# auxboxshield1_7test.net
KiCad netlist of a schematic drawn in EAGLE
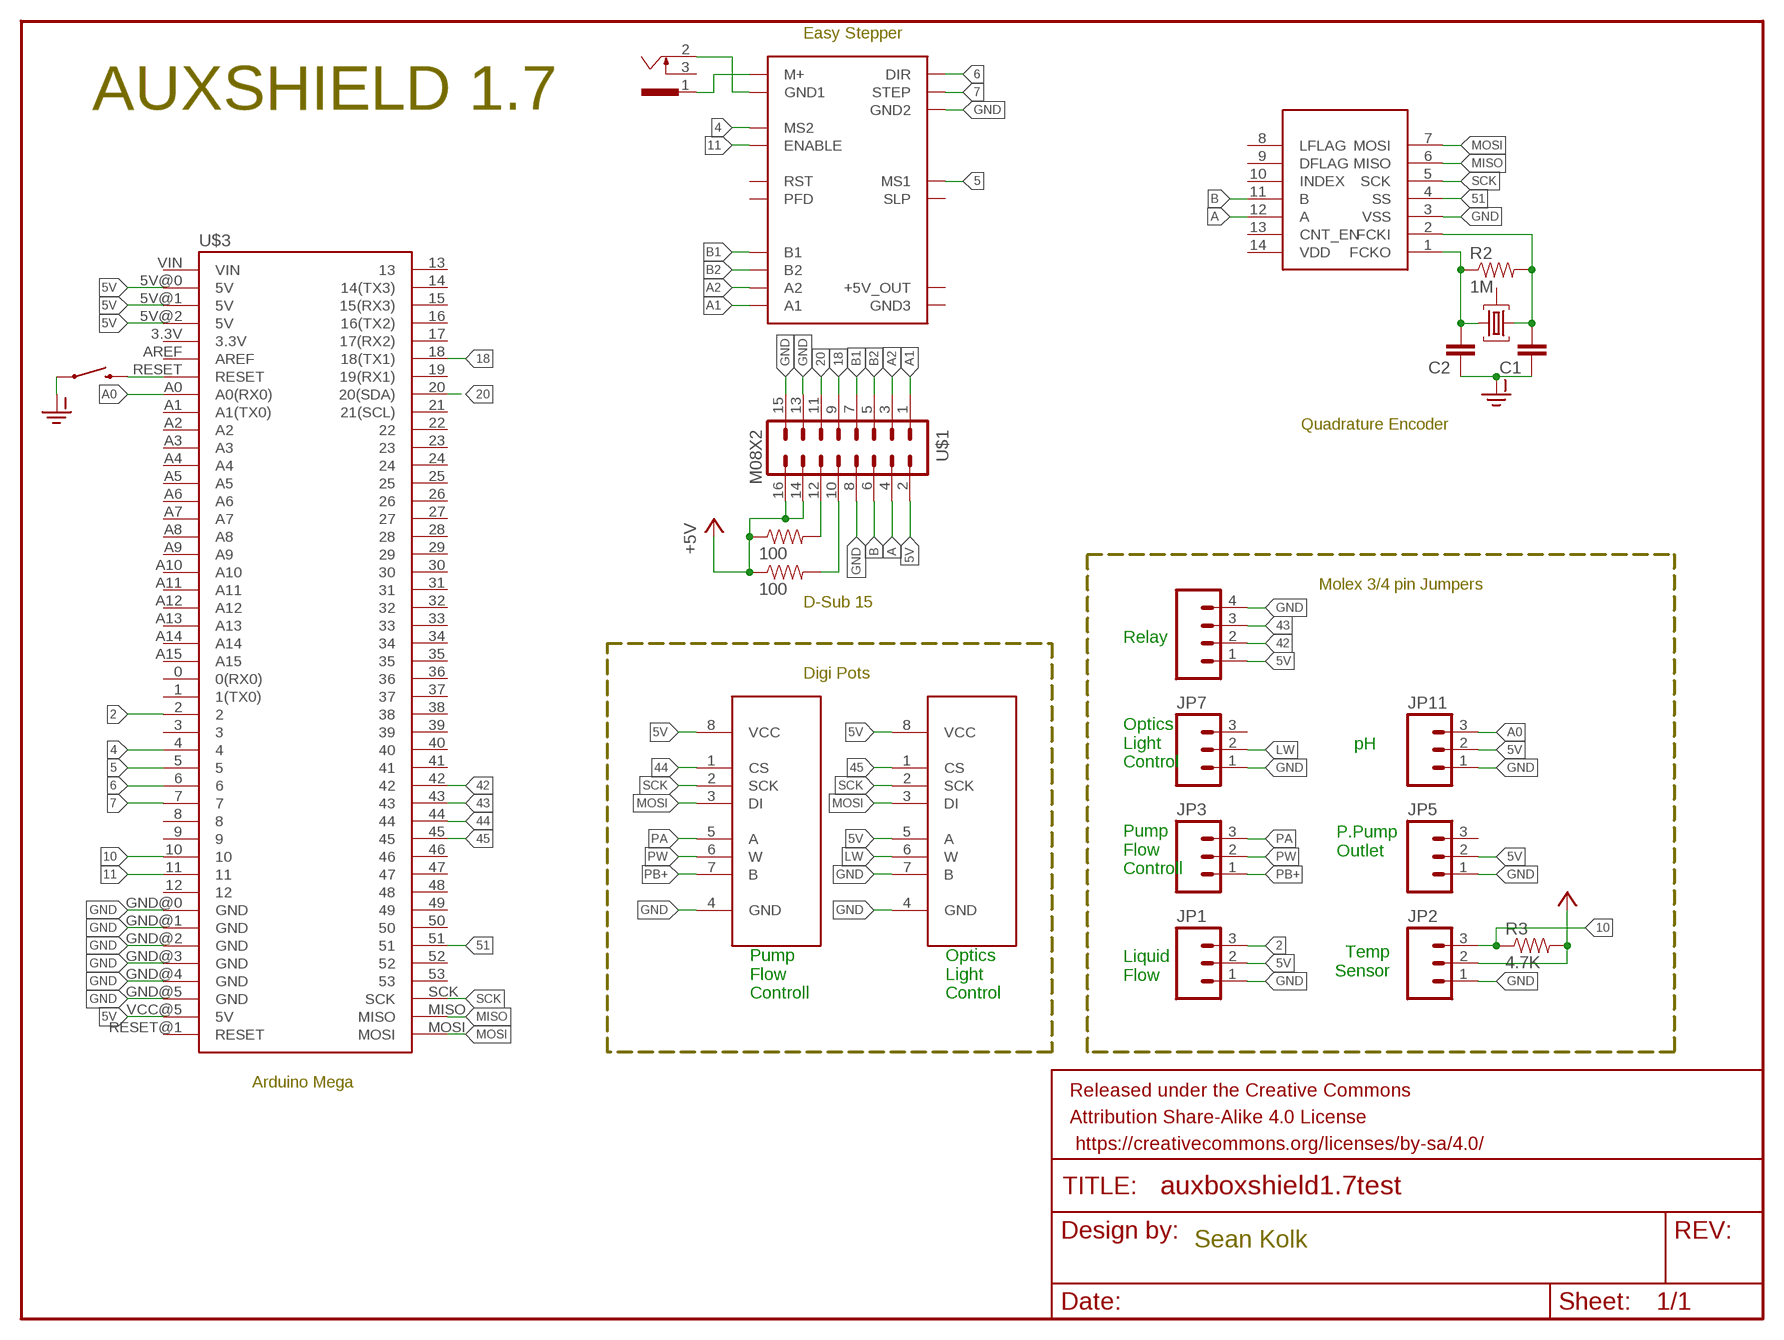
[diagram p0: schematic, sheet 1]

(export (version "E")
  (design (tool "Eeschema 10.0.6"))
  (components
    (comp (ref "C1")
      (value "0.1UF-50V-20%(PTH)KIT-EZ")
      (footprint "eagle-import:CAP-PTH-SMALL-KIT")
      (libsource (lib "eagle-import") (part "0.1UF-50V-20%(PTH)KIT-EZ"))
    )
    (comp (ref "C2")
      (value "0.1UF-50V-20%(PTH)KIT-EZ")
      (footprint "eagle-import:CAP-PTH-SMALL-KIT")
      (libsource (lib "eagle-import") (part "0.1UF-50V-20%(PTH)KIT-EZ"))
    )
    (comp (ref "EASYDRIVER_V44")
      (value "EASYDRIVER_V44")
      (footprint "eagle-import:EASYDRIVER_V44")
      (libsource (lib "eagle-import") (part "EASYDRIVER_V44"))
    )
    (comp (ref "FRAME1")
      (value "FRAME-LETTER")
      (footprint "eagle-import:CREATIVE_COMMONS")
      (libsource (lib "eagle-import") (part "FRAME-LETTER"))
    )
    (comp (ref "JP1")
      (value "M03POLAR")
      (footprint "eagle-import:MOLEX-1X3")
      (libsource (lib "eagle-import") (part "M03POLAR"))
    )
    (comp (ref "JP2")
      (value "M03POLAR")
      (footprint "eagle-import:MOLEX-1X3")
      (libsource (lib "eagle-import") (part "M03POLAR"))
    )
    (comp (ref "JP3")
      (value "M03POLAR")
      (footprint "eagle-import:MOLEX-1X3")
      (libsource (lib "eagle-import") (part "M03POLAR"))
    )
    (comp (ref "JP5")
      (value "M03POLAR")
      (footprint "eagle-import:MOLEX-1X3")
      (libsource (lib "eagle-import") (part "M03POLAR"))
    )
    (comp (ref "JP7")
      (value "M03POLAR")
      (footprint "eagle-import:MOLEX-1X3")
      (libsource (lib "eagle-import") (part "M03POLAR"))
    )
    (comp (ref "JP11")
      (value "M03POLAR")
      (footprint "eagle-import:MOLEX-1X3")
      (libsource (lib "eagle-import") (part "M03POLAR"))
    )
    (comp (ref "PUMPDIGIPOT")
      (value "MCP41XXXDIL")
      (footprint "eagle-import:DIL-08")
      (libsource (lib "eagle-import") (part "MCP41XXXDIL"))
    )
    (comp (ref "QF1")
      (value "21M30AUM5")
      (footprint "eagle-import:UM5")
      (libsource (lib "eagle-import") (part "21MAUM530"))
    )
    (comp (ref "R1")
      (value "100")
      (footprint "eagle-import:AXIAL-0.3")
      (libsource (lib "eagle-import") (part "10OHM-1/4W-5%(PTH)"))
    )
    (comp (ref "R2")
      (value "1M")
      (footprint "eagle-import:AXIAL-0.3")
      (libsource (lib "eagle-import") (part "10OHM-1/4W-5%(PTH)"))
    )
    (comp (ref "R3")
      (value "4.7K")
      (footprint "eagle-import:AXIAL-0.3")
      (libsource (lib "eagle-import") (part "10OHM-1/4W-5%(PTH)"))
    )
    (comp (ref "R4")
      (value "100")
      (footprint "eagle-import:AXIAL-0.3")
      (libsource (lib "eagle-import") (part "10OHM-1/4W-5%(PTH)"))
    )
    (comp (ref "RELAY")
      (value "M04POLAR")
      (footprint "eagle-import:MOLEX-1X4")
      (libsource (lib "eagle-import") (part "M04POLAR"))
    )
    (comp (ref "S1")
      (value "SWITCH-MOMENTARY-2PTH_EZ")
      (footprint "eagle-import:TACTILE-PTH-EZ")
      (libsource (lib "eagle-import") (part "SWITCH-MOMENTARY-2PTH_EZ"))
    )
    (comp (ref "U$1")
      (value "M08X2")
      (footprint "eagle-import:2X8")
      (libsource (lib "eagle-import") (part "M08X2"))
    )
    (comp (ref "U$2")
      (value "LS7366R")
      (footprint "eagle-import:SO014")
      (libsource (lib "eagle-import") (part "LS7366R"))
    )
    (comp (ref "U$3")
      (value "ARDUINO-MEGA-V2")
      (footprint "eagle-import:ARDUINO_MEGA-PRO-5V")
      (libsource (lib "eagle-import") (part "ARDUINO-MEGA-V2"))
    )
    (comp (ref "U1")
      (value "MCP41XXXDIL")
      (footprint "eagle-import:DIL-08")
      (libsource (lib "eagle-import") (part "MCP41XXXDIL"))
    )
    (comp (ref "X1")
      (value "SCD-014A")
      (footprint "eagle-import:SCD-014-A")
      (libsource (lib "eagle-import") (part "SCD-014A"))
    )
  )
  (nets
    (net (code "1") (name "+5V") (class "Default")
      (node (ref "JP2") (pin "2") (pinfunction "2_2") (pintype "passive"))
      (node (ref "R1") (pin "P$1") (pinfunction "1_P$1") (pintype "passive"))
      (node (ref "R3") (pin "P$2") (pinfunction "2_P$2") (pintype "passive"))
      (node (ref "R4") (pin "P$1") (pinfunction "1_P$1") (pintype "passive"))
      (node (ref "U$1") (pin "14") (pinfunction "14_14") (pintype "passive"))
      (node (ref "U$1") (pin "16") (pinfunction "16_16") (pintype "passive"))
    )
    (net (code "2") (name "2") (class "Default")
      (node (ref "JP1") (pin "3") (pinfunction "3_3") (pintype "passive"))
      (node (ref "U$3") (pin "2") (pinfunction "2_2") (pintype "bidirectional"))
    )
    (net (code "3") (name "4") (class "Default")
      (node (ref "EASYDRIVER_V44") (pin "MS2") (pinfunction "MS2_MS2") (pintype "bidirectional"))
      (node (ref "U$3") (pin "4") (pinfunction "4_4") (pintype "bidirectional"))
    )
    (net (code "4") (name "5") (class "Default")
      (node (ref "EASYDRIVER_V44") (pin "MS1") (pinfunction "MS1_MS1") (pintype "bidirectional"))
      (node (ref "U$3") (pin "5") (pinfunction "5_5") (pintype "bidirectional"))
    )
    (net (code "5") (name "5V") (class "Default")
      (node (ref "JP1") (pin "2") (pinfunction "2_2") (pintype "passive"))
      (node (ref "JP11") (pin "2") (pinfunction "2_2") (pintype "passive"))
      (node (ref "JP5") (pin "2") (pinfunction "2_2") (pintype "passive"))
      (node (ref "PUMPDIGIPOT") (pin "8") (pinfunction "VCC_8") (pintype "bidirectional"))
      (node (ref "RELAY") (pin "1") (pinfunction "1_1") (pintype "passive"))
      (node (ref "U$1") (pin "2") (pinfunction "2_2") (pintype "passive"))
      (node (ref "U$3") (pin "5V@0") (pinfunction "5V_5V@0") (pintype "bidirectional"))
      (node (ref "U$3") (pin "5V@1") (pinfunction "5V_5V@1") (pintype "bidirectional"))
      (node (ref "U$3") (pin "5V@2") (pinfunction "5V_5V@2") (pintype "bidirectional"))
      (node (ref "U$3") (pin "VCC@5") (pinfunction "5V_VCC@5") (pintype "bidirectional"))
      (node (ref "U1") (pin "5") (pinfunction "A_5") (pintype "bidirectional"))
      (node (ref "U1") (pin "8") (pinfunction "VCC_8") (pintype "bidirectional"))
    )
    (net (code "6") (name "6") (class "Default")
      (node (ref "EASYDRIVER_V44") (pin "DIR") (pinfunction "DIR_DIR") (pintype "bidirectional"))
      (node (ref "U$3") (pin "6") (pinfunction "6_6") (pintype "bidirectional"))
    )
    (net (code "7") (name "7") (class "Default")
      (node (ref "EASYDRIVER_V44") (pin "STEP") (pinfunction "STEP_STEP") (pintype "bidirectional"))
      (node (ref "U$3") (pin "7") (pinfunction "7_7") (pintype "bidirectional"))
    )
    (net (code "8") (name "10") (class "Default")
      (node (ref "JP2") (pin "3") (pinfunction "3_3") (pintype "passive"))
      (node (ref "R3") (pin "P$1") (pinfunction "1_P$1") (pintype "passive"))
      (node (ref "U$3") (pin "10") (pinfunction "10_10") (pintype "bidirectional"))
    )
    (net (code "9") (name "11") (class "Default")
      (node (ref "EASYDRIVER_V44") (pin "ENABLE") (pinfunction "ENABLE_ENABLE") (pintype "bidirectional"))
      (node (ref "U$3") (pin "11") (pinfunction "11_11") (pintype "bidirectional"))
    )
    (net (code "10") (name "18") (class "Default")
      (node (ref "U$1") (pin "9") (pinfunction "9_9") (pintype "passive"))
      (node (ref "U$3") (pin "18") (pinfunction "18(TX1)_18") (pintype "bidirectional"))
    )
    (net (code "11") (name "20") (class "Default")
      (node (ref "U$1") (pin "11") (pinfunction "11_11") (pintype "passive"))
      (node (ref "U$3") (pin "20") (pinfunction "20(SDA)_20") (pintype "bidirectional"))
    )
    (net (code "12") (name "42") (class "Default")
      (node (ref "RELAY") (pin "2") (pinfunction "2_2") (pintype "passive"))
      (node (ref "U$3") (pin "42") (pinfunction "42_42") (pintype "bidirectional"))
    )
    (net (code "13") (name "43") (class "Default")
      (node (ref "RELAY") (pin "3") (pinfunction "3_3") (pintype "passive"))
      (node (ref "U$3") (pin "43") (pinfunction "43_43") (pintype "bidirectional"))
    )
    (net (code "14") (name "44") (class "Default")
      (node (ref "PUMPDIGIPOT") (pin "1") (pinfunction "CS_1") (pintype "bidirectional"))
      (node (ref "U$3") (pin "44") (pinfunction "44_44") (pintype "bidirectional"))
    )
    (net (code "15") (name "45") (class "Default")
      (node (ref "U$3") (pin "45") (pinfunction "45_45") (pintype "bidirectional"))
      (node (ref "U1") (pin "1") (pinfunction "CS_1") (pintype "bidirectional"))
    )
    (net (code "16") (name "51") (class "Default")
      (node (ref "U$2") (pin "4") (pinfunction "SS_4") (pintype "bidirectional"))
      (node (ref "U$3") (pin "51") (pinfunction "51_51") (pintype "bidirectional"))
    )
    (net (code "17") (name "A") (class "Default")
      (node (ref "U$1") (pin "4") (pinfunction "4_4") (pintype "passive"))
      (node (ref "U$2") (pin "12") (pinfunction "A_12") (pintype "bidirectional"))
    )
    (net (code "18") (name "A0") (class "Default")
      (node (ref "JP11") (pin "3") (pinfunction "3_3") (pintype "passive"))
      (node (ref "U$3") (pin "A0") (pinfunction "A0(RX0)_A0") (pintype "bidirectional"))
    )
    (net (code "19") (name "A1") (class "Default")
      (node (ref "EASYDRIVER_V44") (pin "A1") (pinfunction "A1_A1") (pintype "bidirectional"))
      (node (ref "U$1") (pin "1") (pinfunction "1_1") (pintype "passive"))
    )
    (net (code "20") (name "A2") (class "Default")
      (node (ref "EASYDRIVER_V44") (pin "A2") (pinfunction "A2_A2") (pintype "bidirectional"))
      (node (ref "U$1") (pin "3") (pinfunction "3_3") (pintype "passive"))
    )
    (net (code "21") (name "B") (class "Default")
      (node (ref "U$1") (pin "6") (pinfunction "6_6") (pintype "passive"))
      (node (ref "U$2") (pin "11") (pinfunction "B_11") (pintype "bidirectional"))
    )
    (net (code "22") (name "B1") (class "Default")
      (node (ref "EASYDRIVER_V44") (pin "B1") (pinfunction "B1_B1") (pintype "bidirectional"))
      (node (ref "U$1") (pin "7") (pinfunction "7_7") (pintype "passive"))
    )
    (net (code "23") (name "B2") (class "Default")
      (node (ref "EASYDRIVER_V44") (pin "B2") (pinfunction "B2_B2") (pintype "bidirectional"))
      (node (ref "U$1") (pin "5") (pinfunction "5_5") (pintype "passive"))
    )
    (net (code "24") (name "GND") (class "Default")
      (node (ref "EASYDRIVER_V44") (pin "GND2") (pinfunction "GND2_GND2") (pintype "bidirectional"))
      (node (ref "JP1") (pin "1") (pinfunction "1_1") (pintype "passive"))
      (node (ref "JP11") (pin "1") (pinfunction "1_1") (pintype "passive"))
      (node (ref "JP2") (pin "1") (pinfunction "1_1") (pintype "passive"))
      (node (ref "JP5") (pin "1") (pinfunction "1_1") (pintype "passive"))
      (node (ref "JP7") (pin "1") (pinfunction "1_1") (pintype "passive"))
      (node (ref "PUMPDIGIPOT") (pin "4") (pinfunction "GND_4") (pintype "bidirectional"))
      (node (ref "RELAY") (pin "4") (pinfunction "4_4") (pintype "passive"))
      (node (ref "U$1") (pin "13") (pinfunction "13_13") (pintype "passive"))
      (node (ref "U$1") (pin "15") (pinfunction "15_15") (pintype "passive"))
      (node (ref "U$1") (pin "8") (pinfunction "8_8") (pintype "passive"))
      (node (ref "U$2") (pin "3") (pinfunction "VSS_3") (pintype "bidirectional"))
      (node (ref "U$3") (pin "GND@0") (pinfunction "GND_GND@0") (pintype "bidirectional"))
      (node (ref "U$3") (pin "GND@1") (pinfunction "GND_GND@1") (pintype "bidirectional"))
      (node (ref "U$3") (pin "GND@2") (pinfunction "GND_GND@2") (pintype "bidirectional"))
      (node (ref "U$3") (pin "GND@3") (pinfunction "GND_GND@3") (pintype "bidirectional"))
      (node (ref "U$3") (pin "GND@4") (pinfunction "GND_GND@4") (pintype "bidirectional"))
      (node (ref "U$3") (pin "GND@5") (pinfunction "GND_GND@5") (pintype "bidirectional"))
      (node (ref "U1") (pin "4") (pinfunction "GND_4") (pintype "bidirectional"))
      (node (ref "U1") (pin "7") (pinfunction "B_7") (pintype "bidirectional"))
    )
    (net (code "25") (name "GND-ISO") (class "Default")
      (node (ref "C1") (pin "1") (pinfunction "1_1") (pintype "passive"))
      (node (ref "C2") (pin "1") (pinfunction "1_1") (pintype "passive"))
      (node (ref "S1") (pin "1") (pinfunction "1_1") (pintype "passive"))
    )
    (net (code "26") (name "LW") (class "Default")
      (node (ref "JP7") (pin "2") (pinfunction "2_2") (pintype "passive"))
      (node (ref "U1") (pin "6") (pinfunction "W_6") (pintype "bidirectional"))
    )
    (net (code "27") (name "MISO") (class "Default")
      (node (ref "U$2") (pin "6") (pinfunction "MISO_6") (pintype "bidirectional"))
      (node (ref "U$3") (pin "MISO") (pinfunction "MISO_MISO") (pintype "bidirectional"))
    )
    (net (code "28") (name "MOSI") (class "Default")
      (node (ref "PUMPDIGIPOT") (pin "3") (pinfunction "DI_3") (pintype "bidirectional"))
      (node (ref "U$2") (pin "7") (pinfunction "MOSI_7") (pintype "bidirectional"))
      (node (ref "U$3") (pin "MOSI") (pinfunction "MOSI_MOSI") (pintype "bidirectional"))
      (node (ref "U1") (pin "3") (pinfunction "DI_3") (pintype "bidirectional"))
    )
    (net (code "29") (name "Net-(EASYDRIVER_V44-PadGND1)") (class "Default")
      (node (ref "EASYDRIVER_V44") (pin "GND1") (pinfunction "GND1_GND1") (pintype "bidirectional"))
      (node (ref "X1") (pin "2") (pinfunction "2_2") (pintype "passive"))
    )
    (net (code "30") (name "Net-(EASYDRIVER_V44-PadM+)") (class "Default")
      (node (ref "EASYDRIVER_V44") (pin "M+") (pinfunction "M+_M+") (pintype "bidirectional"))
      (node (ref "X1") (pin "1") (pinfunction "1_1") (pintype "passive"))
    )
    (net (code "31") (name "Net-(R1-2)") (class "Default")
      (node (ref "R1") (pin "P$2") (pinfunction "2_P$2") (pintype "passive"))
      (node (ref "U$1") (pin "10") (pinfunction "10_10") (pintype "passive"))
    )
    (net (code "32") (name "Net-(R2-1)") (class "Default")
      (node (ref "C2") (pin "2") (pinfunction "2_2") (pintype "passive"))
      (node (ref "QF1") (pin "3") (pinfunction "3_3") (pintype "passive"))
      (node (ref "R2") (pin "P$1") (pinfunction "1_P$1") (pintype "passive"))
      (node (ref "U$2") (pin "1") (pinfunction "FCKO_1") (pintype "bidirectional"))
    )
    (net (code "33") (name "Net-(R2-2)") (class "Default")
      (node (ref "C1") (pin "2") (pinfunction "2_2") (pintype "passive"))
      (node (ref "QF1") (pin "1") (pinfunction "1_1") (pintype "passive"))
      (node (ref "R2") (pin "P$2") (pinfunction "2_P$2") (pintype "passive"))
      (node (ref "U$2") (pin "2") (pinfunction "FCKI_2") (pintype "bidirectional"))
    )
    (net (code "34") (name "Net-(R4-2)") (class "Default")
      (node (ref "R4") (pin "P$2") (pinfunction "2_P$2") (pintype "passive"))
      (node (ref "U$1") (pin "12") (pinfunction "12_12") (pintype "passive"))
    )
    (net (code "35") (name "Net-(S1-2)") (class "Default")
      (node (ref "S1") (pin "3") (pinfunction "2_3") (pintype "passive"))
      (node (ref "U$3") (pin "RESET") (pinfunction "RESET_RESET") (pintype "bidirectional"))
    )
    (net (code "36") (name "PA") (class "Default")
      (node (ref "JP3") (pin "3") (pinfunction "3_3") (pintype "passive"))
      (node (ref "PUMPDIGIPOT") (pin "5") (pinfunction "A_5") (pintype "bidirectional"))
    )
    (net (code "37") (name "PB+") (class "Default")
      (node (ref "JP3") (pin "1") (pinfunction "1_1") (pintype "passive"))
      (node (ref "PUMPDIGIPOT") (pin "7") (pinfunction "B_7") (pintype "bidirectional"))
    )
    (net (code "38") (name "PW") (class "Default")
      (node (ref "JP3") (pin "2") (pinfunction "2_2") (pintype "passive"))
      (node (ref "PUMPDIGIPOT") (pin "6") (pinfunction "W_6") (pintype "bidirectional"))
    )
    (net (code "39") (name "SCK") (class "Default")
      (node (ref "PUMPDIGIPOT") (pin "2") (pinfunction "SCK_2") (pintype "bidirectional"))
      (node (ref "U$2") (pin "5") (pinfunction "SCK_5") (pintype "bidirectional"))
      (node (ref "U$3") (pin "SCK") (pinfunction "SCK_SCK") (pintype "bidirectional"))
      (node (ref "U1") (pin "2") (pinfunction "SCK_2") (pintype "bidirectional"))
    )
    (net (code "40") (name "unconnected-(EASYDRIVER_V44-+5V_OUT-PadP$11)") (class "Default")
      (node (ref "EASYDRIVER_V44") (pin "P$11") (pinfunction "+5V_OUT_P$11") (pintype "bidirectional"))
    )
    (net (code "41") (name "unconnected-(EASYDRIVER_V44-PadGND3)") (class "Default")
      (node (ref "EASYDRIVER_V44") (pin "GND3") (pinfunction "GND3_GND3") (pintype "bidirectional"))
    )
    (net (code "42") (name "unconnected-(EASYDRIVER_V44-PadPFD)") (class "Default")
      (node (ref "EASYDRIVER_V44") (pin "PFD") (pinfunction "PFD_PFD") (pintype "bidirectional"))
    )
    (net (code "43") (name "unconnected-(EASYDRIVER_V44-PadRST)") (class "Default")
      (node (ref "EASYDRIVER_V44") (pin "RST") (pinfunction "RST_RST") (pintype "bidirectional"))
    )
    (net (code "44") (name "unconnected-(EASYDRIVER_V44-SLP-PadSLEEP)") (class "Default")
      (node (ref "EASYDRIVER_V44") (pin "SLEEP") (pinfunction "SLP_SLEEP") (pintype "bidirectional"))
    )
    (net (code "45") (name "unconnected-(JP5-Pad3)") (class "Default")
      (node (ref "JP5") (pin "3") (pinfunction "3_3") (pintype "passive"))
    )
    (net (code "46") (name "unconnected-(JP7-Pad3)") (class "Default")
      (node (ref "JP7") (pin "3") (pinfunction "3_3") (pintype "passive"))
    )
    (net (code "47") (name "unconnected-(QF1-Pad2)") (class "Default")
      (node (ref "QF1") (pin "2") (pinfunction "2_2") (pintype "passive"))
    )
    (net (code "48") (name "unconnected-(U$2-CNT_EN-Pad13)") (class "Default")
      (node (ref "U$2") (pin "13") (pinfunction "CNT_EN_13") (pintype "bidirectional"))
    )
    (net (code "49") (name "unconnected-(U$2-DFLAG-Pad9)") (class "Default")
      (node (ref "U$2") (pin "9") (pinfunction "DFLAG_9") (pintype "bidirectional"))
    )
    (net (code "50") (name "unconnected-(U$2-INDEX-Pad10)") (class "Default")
      (node (ref "U$2") (pin "10") (pinfunction "INDEX_10") (pintype "bidirectional"))
    )
    (net (code "51") (name "unconnected-(U$2-LFLAG-Pad8)") (class "Default")
      (node (ref "U$2") (pin "8") (pinfunction "LFLAG_8") (pintype "bidirectional"))
    )
    (net (code "52") (name "unconnected-(U$2-VDD-Pad14)") (class "Default")
      (node (ref "U$2") (pin "14") (pinfunction "VDD_14") (pintype "bidirectional"))
    )
    (net (code "53") (name "unconnected-(U$3-0(RX0)-Pad0)") (class "Default")
      (node (ref "U$3") (pin "0") (pinfunction "0(RX0)_0") (pintype "bidirectional"))
    )
    (net (code "54") (name "unconnected-(U$3-1(TX0)-Pad1)") (class "Default")
      (node (ref "U$3") (pin "1") (pinfunction "1(TX0)_1") (pintype "bidirectional"))
    )
    (net (code "55") (name "unconnected-(U$3-14(TX3)-Pad14)") (class "Default")
      (node (ref "U$3") (pin "14") (pinfunction "14(TX3)_14") (pintype "bidirectional"))
    )
    (net (code "56") (name "unconnected-(U$3-15(RX3)-Pad15)") (class "Default")
      (node (ref "U$3") (pin "15") (pinfunction "15(RX3)_15") (pintype "bidirectional"))
    )
    (net (code "57") (name "unconnected-(U$3-16(TX2)-Pad16)") (class "Default")
      (node (ref "U$3") (pin "16") (pinfunction "16(TX2)_16") (pintype "bidirectional"))
    )
    (net (code "58") (name "unconnected-(U$3-17(RX2)-Pad17)") (class "Default")
      (node (ref "U$3") (pin "17") (pinfunction "17(RX2)_17") (pintype "bidirectional"))
    )
    (net (code "59") (name "unconnected-(U$3-19(RX1)-Pad19)") (class "Default")
      (node (ref "U$3") (pin "19") (pinfunction "19(RX1)_19") (pintype "bidirectional"))
    )
    (net (code "60") (name "unconnected-(U$3-21(SCL)-Pad21)") (class "Default")
      (node (ref "U$3") (pin "21") (pinfunction "21(SCL)_21") (pintype "bidirectional"))
    )
    (net (code "61") (name "unconnected-(U$3-A1(TX0)-PadA1)") (class "Default")
      (node (ref "U$3") (pin "A1") (pinfunction "A1(TX0)_A1") (pintype "bidirectional"))
    )
    (net (code "62") (name "unconnected-(U$3-Pad3)") (class "Default")
      (node (ref "U$3") (pin "3") (pinfunction "3_3") (pintype "bidirectional"))
    )
    (net (code "63") (name "unconnected-(U$3-Pad3.3V)") (class "Default")
      (node (ref "U$3") (pin "3.3V") (pinfunction "3.3V_3.3V") (pintype "bidirectional"))
    )
    (net (code "64") (name "unconnected-(U$3-Pad8)") (class "Default")
      (node (ref "U$3") (pin "8") (pinfunction "8_8") (pintype "bidirectional"))
    )
    (net (code "65") (name "unconnected-(U$3-Pad9)") (class "Default")
      (node (ref "U$3") (pin "9") (pinfunction "9_9") (pintype "bidirectional"))
    )
    (net (code "66") (name "unconnected-(U$3-Pad12)") (class "Default")
      (node (ref "U$3") (pin "12") (pinfunction "12_12") (pintype "bidirectional"))
    )
    (net (code "67") (name "unconnected-(U$3-Pad13)") (class "Default")
      (node (ref "U$3") (pin "13") (pinfunction "13_13") (pintype "bidirectional"))
    )
    (net (code "68") (name "unconnected-(U$3-Pad22)") (class "Default")
      (node (ref "U$3") (pin "22") (pinfunction "22_22") (pintype "bidirectional"))
    )
    (net (code "69") (name "unconnected-(U$3-Pad23)") (class "Default")
      (node (ref "U$3") (pin "23") (pinfunction "23_23") (pintype "bidirectional"))
    )
    (net (code "70") (name "unconnected-(U$3-Pad24)") (class "Default")
      (node (ref "U$3") (pin "24") (pinfunction "24_24") (pintype "bidirectional"))
    )
    (net (code "71") (name "unconnected-(U$3-Pad25)") (class "Default")
      (node (ref "U$3") (pin "25") (pinfunction "25_25") (pintype "bidirectional"))
    )
    (net (code "72") (name "unconnected-(U$3-Pad26)") (class "Default")
      (node (ref "U$3") (pin "26") (pinfunction "26_26") (pintype "bidirectional"))
    )
    (net (code "73") (name "unconnected-(U$3-Pad27)") (class "Default")
      (node (ref "U$3") (pin "27") (pinfunction "27_27") (pintype "bidirectional"))
    )
    (net (code "74") (name "unconnected-(U$3-Pad28)") (class "Default")
      (node (ref "U$3") (pin "28") (pinfunction "28_28") (pintype "bidirectional"))
    )
    (net (code "75") (name "unconnected-(U$3-Pad29)") (class "Default")
      (node (ref "U$3") (pin "29") (pinfunction "29_29") (pintype "bidirectional"))
    )
    (net (code "76") (name "unconnected-(U$3-Pad30)") (class "Default")
      (node (ref "U$3") (pin "30") (pinfunction "30_30") (pintype "bidirectional"))
    )
    (net (code "77") (name "unconnected-(U$3-Pad31)") (class "Default")
      (node (ref "U$3") (pin "31") (pinfunction "31_31") (pintype "bidirectional"))
    )
    (net (code "78") (name "unconnected-(U$3-Pad32)") (class "Default")
      (node (ref "U$3") (pin "32") (pinfunction "32_32") (pintype "bidirectional"))
    )
    (net (code "79") (name "unconnected-(U$3-Pad33)") (class "Default")
      (node (ref "U$3") (pin "33") (pinfunction "33_33") (pintype "bidirectional"))
    )
    (net (code "80") (name "unconnected-(U$3-Pad34)") (class "Default")
      (node (ref "U$3") (pin "34") (pinfunction "34_34") (pintype "bidirectional"))
    )
    (net (code "81") (name "unconnected-(U$3-Pad35)") (class "Default")
      (node (ref "U$3") (pin "35") (pinfunction "35_35") (pintype "bidirectional"))
    )
    (net (code "82") (name "unconnected-(U$3-Pad36)") (class "Default")
      (node (ref "U$3") (pin "36") (pinfunction "36_36") (pintype "bidirectional"))
    )
    (net (code "83") (name "unconnected-(U$3-Pad37)") (class "Default")
      (node (ref "U$3") (pin "37") (pinfunction "37_37") (pintype "bidirectional"))
    )
    (net (code "84") (name "unconnected-(U$3-Pad38)") (class "Default")
      (node (ref "U$3") (pin "38") (pinfunction "38_38") (pintype "bidirectional"))
    )
    (net (code "85") (name "unconnected-(U$3-Pad39)") (class "Default")
      (node (ref "U$3") (pin "39") (pinfunction "39_39") (pintype "bidirectional"))
    )
    (net (code "86") (name "unconnected-(U$3-Pad40)") (class "Default")
      (node (ref "U$3") (pin "40") (pinfunction "40_40") (pintype "bidirectional"))
    )
    (net (code "87") (name "unconnected-(U$3-Pad41)") (class "Default")
      (node (ref "U$3") (pin "41") (pinfunction "41_41") (pintype "bidirectional"))
    )
    (net (code "88") (name "unconnected-(U$3-Pad46)") (class "Default")
      (node (ref "U$3") (pin "46") (pinfunction "46_46") (pintype "bidirectional"))
    )
    (net (code "89") (name "unconnected-(U$3-Pad47)") (class "Default")
      (node (ref "U$3") (pin "47") (pinfunction "47_47") (pintype "bidirectional"))
    )
    (net (code "90") (name "unconnected-(U$3-Pad48)") (class "Default")
      (node (ref "U$3") (pin "48") (pinfunction "48_48") (pintype "bidirectional"))
    )
    (net (code "91") (name "unconnected-(U$3-Pad49)") (class "Default")
      (node (ref "U$3") (pin "49") (pinfunction "49_49") (pintype "bidirectional"))
    )
    (net (code "92") (name "unconnected-(U$3-Pad50)") (class "Default")
      (node (ref "U$3") (pin "50") (pinfunction "50_50") (pintype "bidirectional"))
    )
    (net (code "93") (name "unconnected-(U$3-Pad52)") (class "Default")
      (node (ref "U$3") (pin "52") (pinfunction "52_52") (pintype "bidirectional"))
    )
    (net (code "94") (name "unconnected-(U$3-Pad53)") (class "Default")
      (node (ref "U$3") (pin "53") (pinfunction "53_53") (pintype "bidirectional"))
    )
    (net (code "95") (name "unconnected-(U$3-PadA2)") (class "Default")
      (node (ref "U$3") (pin "A2") (pinfunction "A2_A2") (pintype "bidirectional"))
    )
    (net (code "96") (name "unconnected-(U$3-PadA3)") (class "Default")
      (node (ref "U$3") (pin "A3") (pinfunction "A3_A3") (pintype "bidirectional"))
    )
    (net (code "97") (name "unconnected-(U$3-PadA4)") (class "Default")
      (node (ref "U$3") (pin "A4") (pinfunction "A4_A4") (pintype "bidirectional"))
    )
    (net (code "98") (name "unconnected-(U$3-PadA5)") (class "Default")
      (node (ref "U$3") (pin "A5") (pinfunction "A5_A5") (pintype "bidirectional"))
    )
    (net (code "99") (name "unconnected-(U$3-PadA6)") (class "Default")
      (node (ref "U$3") (pin "A6") (pinfunction "A6_A6") (pintype "bidirectional"))
    )
    (net (code "100") (name "unconnected-(U$3-PadA7)") (class "Default")
      (node (ref "U$3") (pin "A7") (pinfunction "A7_A7") (pintype "bidirectional"))
    )
    (net (code "101") (name "unconnected-(U$3-PadA8)") (class "Default")
      (node (ref "U$3") (pin "A8") (pinfunction "A8_A8") (pintype "bidirectional"))
    )
    (net (code "102") (name "unconnected-(U$3-PadA9)") (class "Default")
      (node (ref "U$3") (pin "A9") (pinfunction "A9_A9") (pintype "bidirectional"))
    )
    (net (code "103") (name "unconnected-(U$3-PadA10)") (class "Default")
      (node (ref "U$3") (pin "A10") (pinfunction "A10_A10") (pintype "bidirectional"))
    )
    (net (code "104") (name "unconnected-(U$3-PadA11)") (class "Default")
      (node (ref "U$3") (pin "A11") (pinfunction "A11_A11") (pintype "bidirectional"))
    )
    (net (code "105") (name "unconnected-(U$3-PadA12)") (class "Default")
      (node (ref "U$3") (pin "A12") (pinfunction "A12_A12") (pintype "bidirectional"))
    )
    (net (code "106") (name "unconnected-(U$3-PadA13)") (class "Default")
      (node (ref "U$3") (pin "A13") (pinfunction "A13_A13") (pintype "bidirectional"))
    )
    (net (code "107") (name "unconnected-(U$3-PadA14)") (class "Default")
      (node (ref "U$3") (pin "A14") (pinfunction "A14_A14") (pintype "bidirectional"))
    )
    (net (code "108") (name "unconnected-(U$3-PadA15)") (class "Default")
      (node (ref "U$3") (pin "A15") (pinfunction "A15_A15") (pintype "bidirectional"))
    )
    (net (code "109") (name "unconnected-(U$3-PadAREF)") (class "Default")
      (node (ref "U$3") (pin "AREF") (pinfunction "AREF_AREF") (pintype "bidirectional"))
    )
    (net (code "110") (name "unconnected-(U$3-PadVIN)") (class "Default")
      (node (ref "U$3") (pin "VIN") (pinfunction "VIN_VIN") (pintype "bidirectional"))
    )
    (net (code "111") (name "unconnected-(U$3-RESET-PadRESET@1)") (class "Default")
      (node (ref "U$3") (pin "RESET@1") (pinfunction "RESET_RESET@1") (pintype "bidirectional"))
    )
    (net (code "112") (name "unconnected-(X1-Pad3)") (class "Default")
      (node (ref "X1") (pin "3") (pinfunction "3_3") (pintype "passive"))
    )
  )
)
